# sduino.net
KiCad netlist of a schematic drawn in EAGLE
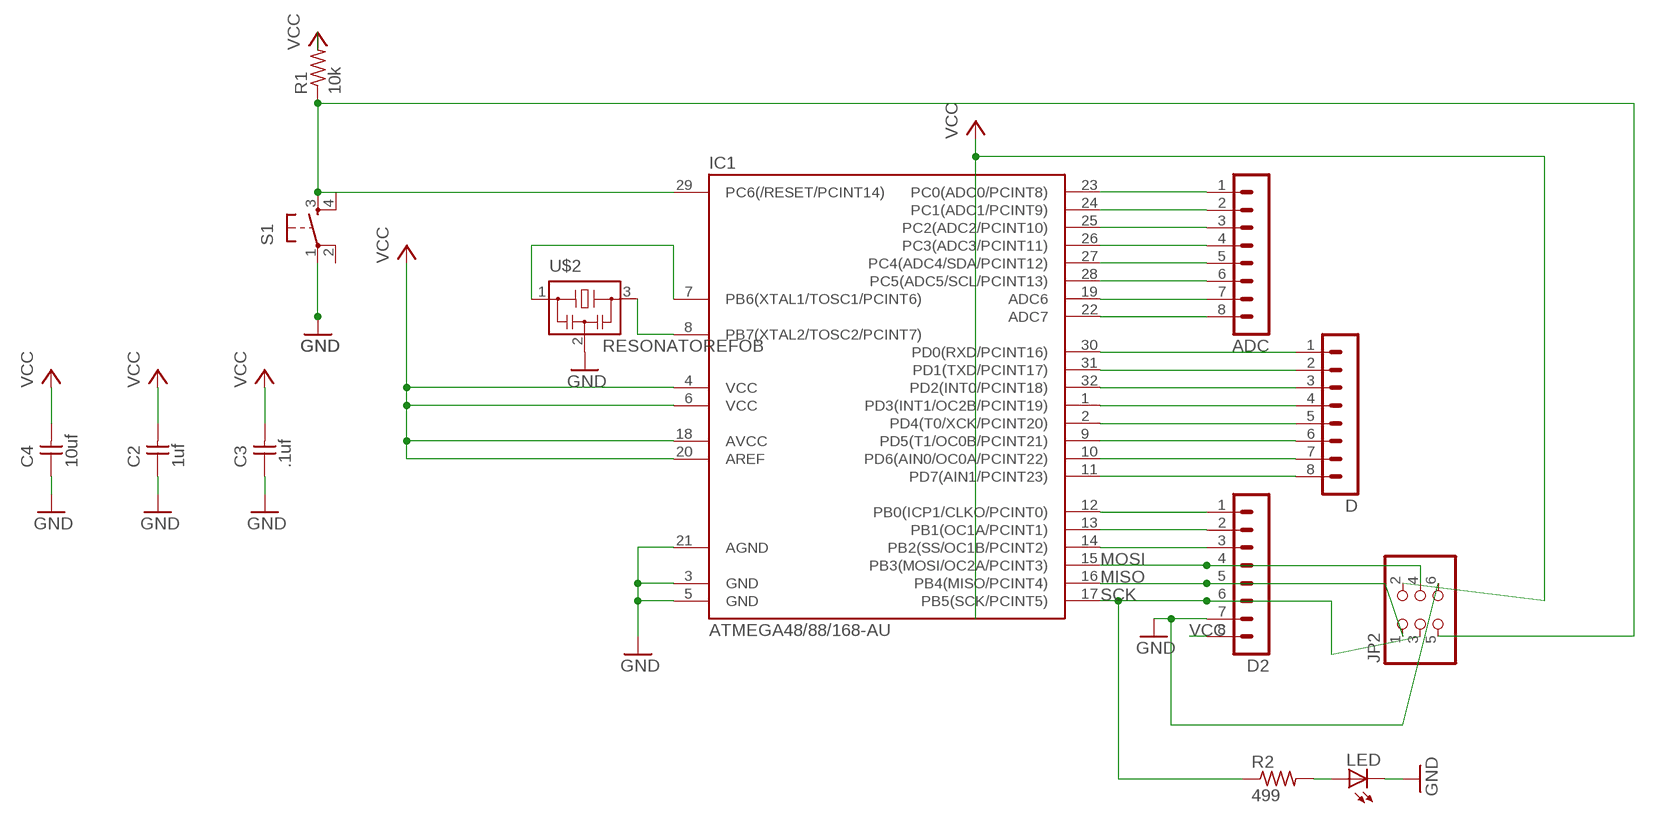
[diagram p0: schematic, sheet 1]

(export (version "E")
  (design (tool "Eeschema 10.0.6"))
  (components
    (comp (ref "ADC")
      (value "MA08-1")
      (footprint "eagle-import:MA08-1")
      (libsource (lib "eagle-import") (part "MA08-1"))
    )
    (comp (ref "C2")
      (value "1uf")
      (footprint "eagle-import:1206")
      (libsource (lib "eagle-import") (part "UNPOLARIZED_CAPACITOR1206"))
    )
    (comp (ref "C3")
      (value ".1uf")
      (footprint "eagle-import:1206")
      (libsource (lib "eagle-import") (part "UNPOLARIZED_CAPACITOR1206"))
    )
    (comp (ref "C4")
      (value "10uf")
      (footprint "eagle-import:1206")
      (libsource (lib "eagle-import") (part "UNPOLARIZED_CAPACITOR1206"))
    )
    (comp (ref "D")
      (value "MA08-1")
      (footprint "eagle-import:MA08-1")
      (libsource (lib "eagle-import") (part "MA08-1"))
    )
    (comp (ref "D2")
      (value "MA08-1")
      (footprint "eagle-import:MA08-1")
      (libsource (lib "eagle-import") (part "MA08-1"))
    )
    (comp (ref "IC1")
      (value "ATMEGA48/88/168-AU")
      (footprint "eagle-import:TQFP32-08")
      (libsource (lib "eagle-import") (part "ATMEGA48/88/168-AU"))
    )
    (comp (ref "JP2")
      (value "PINHD-2X3-SMD")
      (footprint "eagle-import:2X03SMD")
      (libsource (lib "eagle-import") (part "PINHD-2X3-SMD"))
    )
    (comp (ref "LED")
      (value "LED1206")
      (footprint "eagle-import:1206")
      (libsource (lib "eagle-import") (part "LED1206"))
    )
    (comp (ref "R1")
      (value "10k")
      (footprint "eagle-import:1206")
      (libsource (lib "eagle-import") (part "RESISTOR1206"))
    )
    (comp (ref "R2")
      (value "499")
      (footprint "eagle-import:1206")
      (libsource (lib "eagle-import") (part "RESISTOR1206"))
    )
    (comp (ref "S1")
      (value "6MM_SWITCH6MM_SWITCH")
      (footprint "eagle-import:6MM_SWITCH")
      (libsource (lib "eagle-import") (part "6MM_SWITCH6MM_SWITCH"))
    )
    (comp (ref "U$2")
      (value "RESONATOREFOB")
      (footprint "eagle-import:EFOBM")
      (libsource (lib "eagle-import") (part "RESONATOREFOB"))
    )
  )
  (nets
    (net (code "1") (name "/MISO") (class "Default")
      (node (ref "D2") (pin "5") (pinfunction "5_5") (pintype "passive"))
      (node (ref "IC1") (pin "16") (pinfunction "PB4(MISO/PCINT4)_16") (pintype "bidirectional"))
      (node (ref "JP2") (pin "1") (pinfunction "1_1") (pintype "passive"))
    )
    (net (code "2") (name "/MOSI") (class "Default")
      (node (ref "D2") (pin "4") (pinfunction "4_4") (pintype "passive"))
      (node (ref "IC1") (pin "15") (pinfunction "PB3(MOSI/OC2A/PCINT3)_15") (pintype "bidirectional"))
      (node (ref "JP2") (pin "4") (pinfunction "4_4") (pintype "passive"))
    )
    (net (code "3") (name "/SCK") (class "Default")
      (node (ref "D2") (pin "6") (pinfunction "6_6") (pintype "passive"))
      (node (ref "IC1") (pin "17") (pinfunction "PB5(SCK/PCINT5)_17") (pintype "bidirectional"))
      (node (ref "JP2") (pin "3") (pinfunction "3_3") (pintype "passive"))
      (node (ref "R2") (pin "1") (pinfunction "1_1") (pintype "passive"))
    )
    (net (code "4") (name "GND") (class "Default")
      (node (ref "C2") (pin "1") (pinfunction "1_1") (pintype "passive"))
      (node (ref "C3") (pin "1") (pinfunction "1_1") (pintype "passive"))
      (node (ref "C4") (pin "1") (pinfunction "1_1") (pintype "passive"))
      (node (ref "D2") (pin "7") (pinfunction "7_7") (pintype "passive"))
      (node (ref "IC1") (pin "21") (pinfunction "AGND_21") (pintype "power_in"))
      (node (ref "IC1") (pin "3") (pinfunction "GND_3") (pintype "power_in"))
      (node (ref "IC1") (pin "5") (pinfunction "GND_5") (pintype "power_in"))
      (node (ref "JP2") (pin "6") (pinfunction "6_6") (pintype "passive"))
      (node (ref "LED") (pin "2") (pinfunction "C_2") (pintype "passive"))
      (node (ref "S1") (pin "1") (pinfunction "P_1") (pintype "passive"))
      (node (ref "U$2") (pin "2") (pinfunction "2_2") (pintype "passive"))
    )
    (net (code "5") (name "Net-(IC1-ADC6)") (class "Default")
      (node (ref "ADC") (pin "7") (pinfunction "7_7") (pintype "passive"))
      (node (ref "IC1") (pin "19") (pinfunction "ADC6_19") (pintype "passive"))
    )
    (net (code "6") (name "Net-(IC1-ADC7)") (class "Default")
      (node (ref "ADC") (pin "8") (pinfunction "8_8") (pintype "passive"))
      (node (ref "IC1") (pin "22") (pinfunction "ADC7_22") (pintype "passive"))
    )
    (net (code "7") (name "Net-(IC1-PB0(ICP1{slash}CLKO{slash}PCINT0))") (class "Default")
      (node (ref "D2") (pin "1") (pinfunction "1_1") (pintype "passive"))
      (node (ref "IC1") (pin "12") (pinfunction "PB0(ICP1/CLKO/PCINT0)_12") (pintype "bidirectional"))
    )
    (net (code "8") (name "Net-(IC1-PB1(OC1A{slash}PCINT1))") (class "Default")
      (node (ref "D2") (pin "2") (pinfunction "2_2") (pintype "passive"))
      (node (ref "IC1") (pin "13") (pinfunction "PB1(OC1A/PCINT1)_13") (pintype "bidirectional"))
    )
    (net (code "9") (name "Net-(IC1-PB2(SS{slash}OC1B{slash}PCINT2))") (class "Default")
      (node (ref "D2") (pin "3") (pinfunction "3_3") (pintype "passive"))
      (node (ref "IC1") (pin "14") (pinfunction "PB2(SS/OC1B/PCINT2)_14") (pintype "bidirectional"))
    )
    (net (code "10") (name "Net-(IC1-PB6(XTAL1{slash}TOSC1{slash}PCINT6))") (class "Default")
      (node (ref "IC1") (pin "7") (pinfunction "PB6(XTAL1/TOSC1/PCINT6)_7") (pintype "bidirectional"))
      (node (ref "U$2") (pin "1") (pinfunction "1_1") (pintype "passive"))
    )
    (net (code "11") (name "Net-(IC1-PB7(XTAL2{slash}TOSC2{slash}PCINT7))") (class "Default")
      (node (ref "IC1") (pin "8") (pinfunction "PB7(XTAL2/TOSC2/PCINT7)_8") (pintype "bidirectional"))
      (node (ref "U$2") (pin "3") (pinfunction "3_3") (pintype "passive"))
    )
    (net (code "12") (name "Net-(IC1-PC0(ADC0{slash}PCINT8))") (class "Default")
      (node (ref "ADC") (pin "1") (pinfunction "1_1") (pintype "passive"))
      (node (ref "IC1") (pin "23") (pinfunction "PC0(ADC0/PCINT8)_23") (pintype "bidirectional"))
    )
    (net (code "13") (name "Net-(IC1-PC1(ADC1{slash}PCINT9))") (class "Default")
      (node (ref "ADC") (pin "2") (pinfunction "2_2") (pintype "passive"))
      (node (ref "IC1") (pin "24") (pinfunction "PC1(ADC1/PCINT9)_24") (pintype "bidirectional"))
    )
    (net (code "14") (name "Net-(IC1-PC2(ADC2{slash}PCINT10))") (class "Default")
      (node (ref "ADC") (pin "3") (pinfunction "3_3") (pintype "passive"))
      (node (ref "IC1") (pin "25") (pinfunction "PC2(ADC2/PCINT10)_25") (pintype "bidirectional"))
    )
    (net (code "15") (name "Net-(IC1-PC3(ADC3{slash}PCINT11))") (class "Default")
      (node (ref "ADC") (pin "4") (pinfunction "4_4") (pintype "passive"))
      (node (ref "IC1") (pin "26") (pinfunction "PC3(ADC3/PCINT11)_26") (pintype "bidirectional"))
    )
    (net (code "16") (name "Net-(IC1-PC4(ADC4{slash}SDA{slash}PCINT12))") (class "Default")
      (node (ref "ADC") (pin "5") (pinfunction "5_5") (pintype "passive"))
      (node (ref "IC1") (pin "27") (pinfunction "PC4(ADC4/SDA/PCINT12)_27") (pintype "bidirectional"))
    )
    (net (code "17") (name "Net-(IC1-PC5(ADC5{slash}SCL{slash}PCINT13))") (class "Default")
      (node (ref "ADC") (pin "6") (pinfunction "6_6") (pintype "passive"))
      (node (ref "IC1") (pin "28") (pinfunction "PC5(ADC5/SCL/PCINT13)_28") (pintype "bidirectional"))
    )
    (net (code "18") (name "Net-(IC1-PC6({slash}RESET{slash}PCINT14))") (class "Default")
      (node (ref "IC1") (pin "29") (pinfunction "PC6(/RESET/PCINT14)_29") (pintype "bidirectional"))
      (node (ref "JP2") (pin "5") (pinfunction "5_5") (pintype "passive"))
      (node (ref "R1") (pin "1") (pinfunction "1_1") (pintype "passive"))
      (node (ref "S1") (pin "3") (pinfunction "S_3") (pintype "passive"))
    )
    (net (code "19") (name "Net-(IC1-PD0(RXD{slash}PCINT16))") (class "Default")
      (node (ref "D") (pin "1") (pinfunction "1_1") (pintype "passive"))
      (node (ref "IC1") (pin "30") (pinfunction "PD0(RXD/PCINT16)_30") (pintype "bidirectional"))
    )
    (net (code "20") (name "Net-(IC1-PD1(TXD{slash}PCINT17))") (class "Default")
      (node (ref "D") (pin "2") (pinfunction "2_2") (pintype "passive"))
      (node (ref "IC1") (pin "31") (pinfunction "PD1(TXD/PCINT17)_31") (pintype "bidirectional"))
    )
    (net (code "21") (name "Net-(IC1-PD2(INT0{slash}PCINT18))") (class "Default")
      (node (ref "D") (pin "3") (pinfunction "3_3") (pintype "passive"))
      (node (ref "IC1") (pin "32") (pinfunction "PD2(INT0/PCINT18)_32") (pintype "bidirectional"))
    )
    (net (code "22") (name "Net-(IC1-PD3(INT1{slash}OC2B{slash}PCINT19))") (class "Default")
      (node (ref "D") (pin "4") (pinfunction "4_4") (pintype "passive"))
      (node (ref "IC1") (pin "1") (pinfunction "PD3(INT1/OC2B/PCINT19)_1") (pintype "bidirectional"))
    )
    (net (code "23") (name "Net-(IC1-PD4(T0{slash}XCK{slash}PCINT20))") (class "Default")
      (node (ref "D") (pin "5") (pinfunction "5_5") (pintype "passive"))
      (node (ref "IC1") (pin "2") (pinfunction "PD4(T0/XCK/PCINT20)_2") (pintype "bidirectional"))
    )
    (net (code "24") (name "Net-(IC1-PD5(T1{slash}OC0B{slash}PCINT21))") (class "Default")
      (node (ref "D") (pin "6") (pinfunction "6_6") (pintype "passive"))
      (node (ref "IC1") (pin "9") (pinfunction "PD5(T1/OC0B/PCINT21)_9") (pintype "bidirectional"))
    )
    (net (code "25") (name "Net-(IC1-PD6(AIN0{slash}OC0A{slash}PCINT22))") (class "Default")
      (node (ref "D") (pin "7") (pinfunction "7_7") (pintype "passive"))
      (node (ref "IC1") (pin "10") (pinfunction "PD6(AIN0/OC0A/PCINT22)_10") (pintype "bidirectional"))
    )
    (net (code "26") (name "Net-(IC1-PD7(AIN1{slash}PCINT23))") (class "Default")
      (node (ref "D") (pin "8") (pinfunction "8_8") (pintype "passive"))
      (node (ref "IC1") (pin "11") (pinfunction "PD7(AIN1/PCINT23)_11") (pintype "bidirectional"))
    )
    (net (code "27") (name "Net-(LED-A)") (class "Default")
      (node (ref "LED") (pin "1") (pinfunction "A_1") (pintype "passive"))
      (node (ref "R2") (pin "2") (pinfunction "2_2") (pintype "passive"))
    )
    (net (code "28") (name "VCC") (class "Default")
      (node (ref "C2") (pin "2") (pinfunction "2_2") (pintype "passive"))
      (node (ref "C3") (pin "2") (pinfunction "2_2") (pintype "passive"))
      (node (ref "C4") (pin "2") (pinfunction "2_2") (pintype "passive"))
      (node (ref "D2") (pin "8") (pinfunction "8_8") (pintype "passive"))
      (node (ref "IC1") (pin "18") (pinfunction "AVCC_18") (pintype "passive"))
      (node (ref "IC1") (pin "20") (pinfunction "AREF_20") (pintype "passive"))
      (node (ref "IC1") (pin "4") (pinfunction "VCC_4") (pintype "power_in"))
      (node (ref "IC1") (pin "6") (pinfunction "VCC_6") (pintype "power_in"))
      (node (ref "JP2") (pin "2") (pinfunction "2_2") (pintype "passive"))
      (node (ref "R1") (pin "2") (pinfunction "2_2") (pintype "passive"))
    )
    (net (code "29") (name "unconnected-(S1-P1-Pad2)") (class "Default")
      (node (ref "S1") (pin "2") (pinfunction "P1_2") (pintype "passive"))
    )
    (net (code "30") (name "unconnected-(S1-S1-Pad4)") (class "Default")
      (node (ref "S1") (pin "4") (pinfunction "S1_4") (pintype "passive"))
    )
  )
)
